# Power_6V.net
KiCad netlist of a schematic drawn in Altium Designer
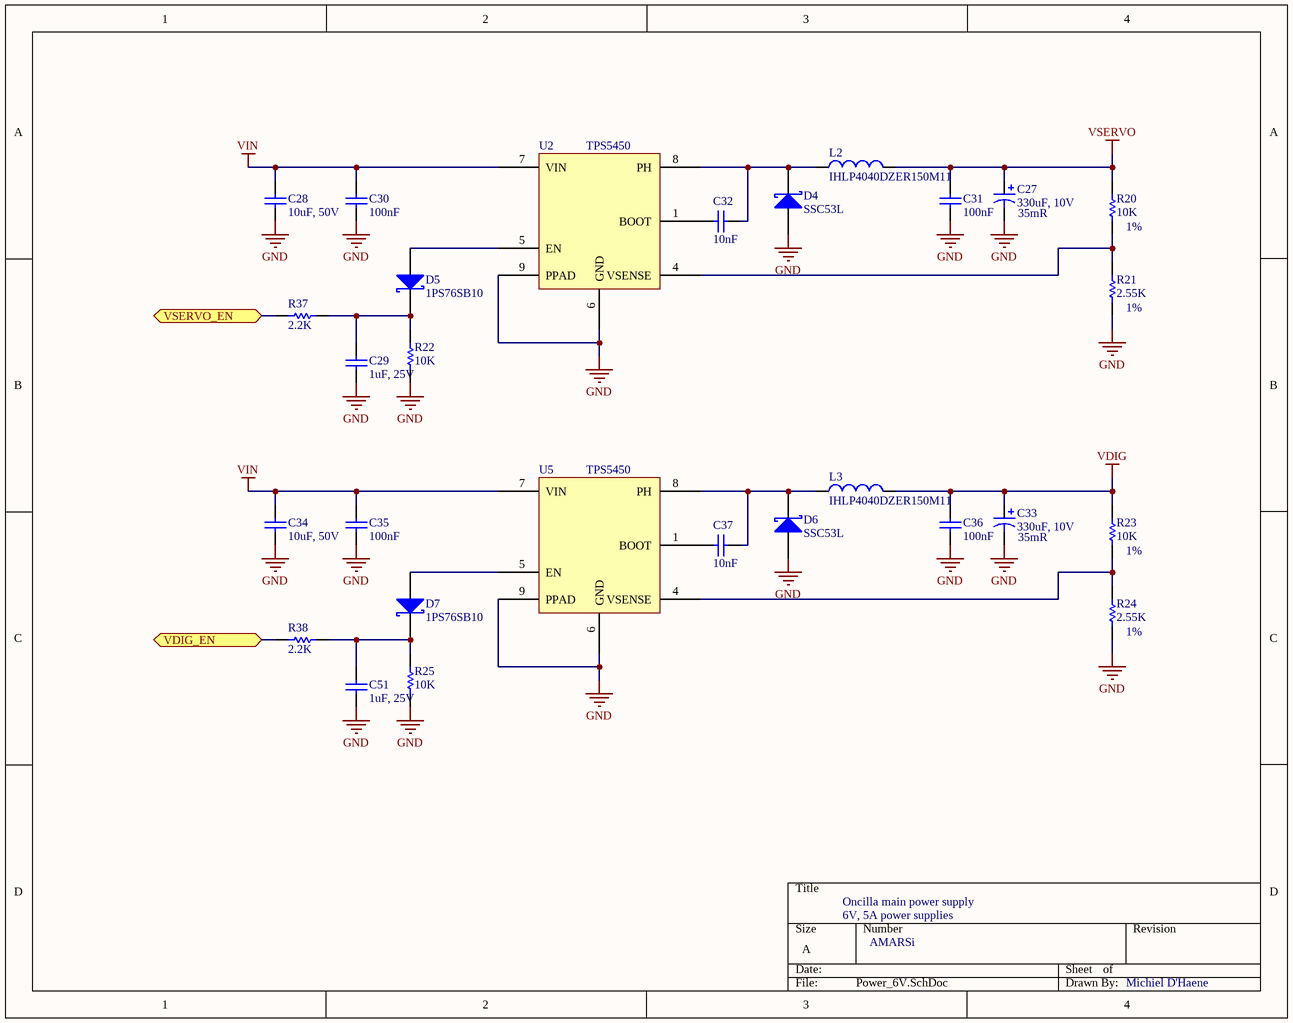
[diagram p0: Power_6V.SchDoc]

(export (version "E")
  (design (tool "Eeschema 10.0.6"))
  (components
    (comp (ref "C27")
      (value "330uF, 10V")
      (footprint "7343")
      (fields (field (name "ESR") "35mR") (field (name "PUBLISHER") "Altium Limited"))
      (libsource (lib "Vishay Sprague Tantalum Chip Capacitor") (part "255D157X06R3D2T045"))
    )
    (comp (ref "C28")
      (value "10uF, 50V")
      (footprint "CAPC3216L")
      (description "Capacitor (Semiconductor SIM Model)")
      (fields (field (name "PUBLISHER") "Altium Limited"))
      (libsource (lib "Miscellaneous Devices") (part "Cap Semi"))
    )
    (comp (ref "C29")
      (value "1uF, 25V")
      (footprint "CAPC1608L")
      (description "Capacitor (Semiconductor SIM Model)")
      (fields (field (name "PUBLISHER") "Altium Limited"))
      (libsource (lib "Miscellaneous Devices") (part "Cap Semi"))
    )
    (comp (ref "C30")
      (value "100nF")
      (footprint "CAPC1608L")
      (description "Capacitor (Semiconductor SIM Model)")
      (fields (field (name "PUBLISHER") "Altium Limited"))
      (libsource (lib "Miscellaneous Devices") (part "Cap Semi"))
    )
    (comp (ref "C31")
      (value "100nF")
      (footprint "CAPC1608L")
      (description "Capacitor (Semiconductor SIM Model)")
      (fields (field (name "PUBLISHER") "Altium Limited"))
      (libsource (lib "Miscellaneous Devices") (part "Cap Semi"))
    )
    (comp (ref "C32")
      (value "10nF")
      (footprint "CAPC1608L")
      (description "Capacitor (Semiconductor SIM Model)")
      (fields (field (name "PUBLISHER") "Altium Limited"))
      (libsource (lib "Miscellaneous Devices") (part "Cap Semi"))
    )
    (comp (ref "C33")
      (value "330uF, 10V")
      (footprint "7343")
      (fields (field (name "ESR") "35mR") (field (name "PUBLISHER") "Altium Limited"))
      (libsource (lib "Vishay Sprague Tantalum Chip Capacitor") (part "255D157X06R3D2T045"))
    )
    (comp (ref "C34")
      (value "10uF, 50V")
      (footprint "CAPC3216L")
      (description "Capacitor (Semiconductor SIM Model)")
      (fields (field (name "PUBLISHER") "Altium Limited"))
      (libsource (lib "Miscellaneous Devices") (part "Cap Semi"))
    )
    (comp (ref "C35")
      (value "100nF")
      (footprint "CAPC1608L")
      (description "Capacitor (Semiconductor SIM Model)")
      (fields (field (name "PUBLISHER") "Altium Limited"))
      (libsource (lib "Miscellaneous Devices") (part "Cap Semi"))
    )
    (comp (ref "C36")
      (value "100nF")
      (footprint "CAPC1608L")
      (description "Capacitor (Semiconductor SIM Model)")
      (fields (field (name "PUBLISHER") "Altium Limited"))
      (libsource (lib "Miscellaneous Devices") (part "Cap Semi"))
    )
    (comp (ref "C37")
      (value "10nF")
      (footprint "CAPC1608L")
      (description "Capacitor (Semiconductor SIM Model)")
      (fields (field (name "PUBLISHER") "Altium Limited"))
      (libsource (lib "Miscellaneous Devices") (part "Cap Semi"))
    )
    (comp (ref "C51")
      (value "1uF, 25V")
      (footprint "CAPC1608L")
      (description "Capacitor (Semiconductor SIM Model)")
      (fields (field (name "PUBLISHER") "Altium Limited"))
      (libsource (lib "Miscellaneous Devices") (part "Cap Semi"))
    )
    (comp (ref "D4")
      (value "SSC53L")
      (footprint "SMC")
      (description "Schottky Rectifier")
      (fields (field (name "PUBLISHER") "Altium Limited"))
      (libsource (lib "IR Rectifier - Schottky") (part "30BQ040"))
    )
    (comp (ref "D5")
      (value "1PS76SB10")
      (footprint "SOD323")
      (description "Schottky Barrier Diode")
      (fields (field (name "PUBLISHER") "Altium Limited"))
      (libsource (lib "Philips Discrete Diode - Schottky") (part "1PS76SB10"))
    )
    (comp (ref "D6")
      (value "SSC53L")
      (footprint "SMC")
      (description "Schottky Rectifier")
      (fields (field (name "PUBLISHER") "Altium Limited"))
      (libsource (lib "IR Rectifier - Schottky") (part "30BQ040"))
    )
    (comp (ref "D7")
      (value "1PS76SB10")
      (footprint "SOD323")
      (description "Schottky Barrier Diode")
      (fields (field (name "PUBLISHER") "Altium Limited"))
      (libsource (lib "Philips Discrete Diode - Schottky") (part "1PS76SB10"))
    )
    (comp (ref "L2")
      (value "IHLP4040DZER150M11")
      (footprint "IHLP-4040DZ")
      (libsource (lib "New_library") (part "Inductor"))
    )
    (comp (ref "L3")
      (value "IHLP4040DZER150M11")
      (footprint "IHLP-4040DZ")
      (libsource (lib "New_library") (part "Inductor"))
    )
    (comp (ref "R20")
      (value "10K")
      (footprint "RESC1608L")
      (description "Semiconductor Resistor")
      (fields
        (field (name "PRECISION") "1%")
        (field (name "Comment") "10k, 1%")
        (field (name "PUBLISHER") "Altium Limited")
      )
      (libsource (lib "Miscellaneous Devices") (part "Res Semi"))
    )
    (comp (ref "R21")
      (value "2.55K")
      (footprint "RESC1608L")
      (description "Semiconductor Resistor")
      (fields
        (field (name "PRECISION") "1%")
        (field (name "Comment") "2.55k, 1%")
        (field (name "PUBLISHER") "Altium Limited")
      )
      (libsource (lib "Miscellaneous Devices") (part "Res Semi"))
    )
    (comp (ref "R22")
      (value "10K")
      (footprint "RESC1608L")
      (description "Semiconductor Resistor")
      (fields (field (name "Comment") "10k") (field (name "PUBLISHER") "Altium Limited"))
      (libsource (lib "Miscellaneous Devices") (part "Res Semi"))
    )
    (comp (ref "R23")
      (value "10K")
      (footprint "RESC1608L")
      (description "Semiconductor Resistor")
      (fields
        (field (name "PRECISION") "1%")
        (field (name "Comment") "10k, 1%")
        (field (name "PUBLISHER") "Altium Limited")
      )
      (libsource (lib "Miscellaneous Devices") (part "Res Semi"))
    )
    (comp (ref "R24")
      (value "2.55K")
      (footprint "RESC1608L")
      (description "Semiconductor Resistor")
      (fields
        (field (name "PRECISION") "1%")
        (field (name "Comment") "2.55k, 1%")
        (field (name "PUBLISHER") "Altium Limited")
      )
      (libsource (lib "Miscellaneous Devices") (part "Res Semi"))
    )
    (comp (ref "R25")
      (value "10K")
      (footprint "RESC1608L")
      (description "Semiconductor Resistor")
      (fields (field (name "Comment") "10k") (field (name "PUBLISHER") "Altium Limited"))
      (libsource (lib "Miscellaneous Devices") (part "Res Semi"))
    )
    (comp (ref "R37")
      (value "2.2K")
      (footprint "RESC1608L")
      (description "Semiconductor Resistor")
      (fields (field (name "Comment") "2.2k") (field (name "PUBLISHER") "Altium Limited"))
      (libsource (lib "Miscellaneous Devices") (part "Res Semi"))
    )
    (comp (ref "R38")
      (value "2.2K")
      (footprint "RESC1608L")
      (description "Semiconductor Resistor")
      (fields (field (name "Comment") "2.2k") (field (name "PUBLISHER") "Altium Limited"))
      (libsource (lib "Miscellaneous Devices") (part "Res Semi"))
    )
    (comp (ref "U2")
      (value "TPS5450")
      (footprint "SOIC8 POWERPAD")
      (libsource (lib "New_library") (part "TPS5450"))
    )
    (comp (ref "U5")
      (value "TPS5450")
      (footprint "SOIC8 POWERPAD")
      (libsource (lib "New_library") (part "TPS5450"))
    )
  )
  (nets
    (net (code "1") (name "/VDIG_EN") (class "Default")
      (node (ref "R38") (pin "2") (pinfunction "2_2") (pintype "passive"))
    )
    (net (code "2") (name "/VSERVO_EN") (class "Default")
      (node (ref "R37") (pin "2") (pinfunction "2_2") (pintype "passive"))
    )
    (net (code "3") (name "GND") (class "Default")
      (node (ref "C27") (pin "2") (pinfunction "2_2") (pintype "passive"))
      (node (ref "C28") (pin "1") (pinfunction "1_1") (pintype "passive"))
      (node (ref "C29") (pin "1") (pinfunction "1_1") (pintype "passive"))
      (node (ref "C30") (pin "1") (pinfunction "1_1") (pintype "passive"))
      (node (ref "C31") (pin "1") (pinfunction "1_1") (pintype "passive"))
      (node (ref "C33") (pin "2") (pinfunction "2_2") (pintype "passive"))
      (node (ref "C34") (pin "1") (pinfunction "1_1") (pintype "passive"))
      (node (ref "C35") (pin "1") (pinfunction "1_1") (pintype "passive"))
      (node (ref "C36") (pin "1") (pinfunction "1_1") (pintype "passive"))
      (node (ref "C51") (pin "1") (pinfunction "1_1") (pintype "passive"))
      (node (ref "D4") (pin "1") (pinfunction "A_1") (pintype "passive"))
      (node (ref "D6") (pin "1") (pinfunction "A_1") (pintype "passive"))
      (node (ref "R21") (pin "1") (pinfunction "1_1") (pintype "passive"))
      (node (ref "R22") (pin "1") (pinfunction "1_1") (pintype "passive"))
      (node (ref "R24") (pin "1") (pinfunction "1_1") (pintype "passive"))
      (node (ref "R25") (pin "1") (pinfunction "1_1") (pintype "passive"))
      (node (ref "U2") (pin "6") (pinfunction "GND_6") (pintype "passive"))
      (node (ref "U2") (pin "9") (pinfunction "PPAD_9") (pintype "passive"))
      (node (ref "U5") (pin "6") (pinfunction "GND_6") (pintype "passive"))
      (node (ref "U5") (pin "9") (pinfunction "PPAD_9") (pintype "passive"))
    )
    (net (code "4") (name "Net-(D4-K)") (class "Default")
      (node (ref "C32") (pin "2") (pinfunction "2_2") (pintype "passive"))
      (node (ref "D4") (pin "2") (pinfunction "K_2") (pintype "passive"))
      (node (ref "L2") (pin "1") (pinfunction "1_1") (pintype "passive"))
      (node (ref "U2") (pin "8") (pinfunction "PH_8") (pintype "passive"))
    )
    (net (code "5") (name "Net-(D5-A)") (class "Default")
      (node (ref "D5") (pin "2") (pinfunction "A_2") (pintype "passive"))
      (node (ref "U2") (pin "5") (pinfunction "EN_5") (pintype "passive"))
    )
    (net (code "6") (name "Net-(D5-K)") (class "Default")
      (node (ref "C29") (pin "2") (pinfunction "2_2") (pintype "passive"))
      (node (ref "D5") (pin "1") (pinfunction "K_1") (pintype "passive"))
      (node (ref "R22") (pin "2") (pinfunction "2_2") (pintype "passive"))
      (node (ref "R37") (pin "1") (pinfunction "1_1") (pintype "passive"))
    )
    (net (code "7") (name "Net-(D6-K)") (class "Default")
      (node (ref "C37") (pin "2") (pinfunction "2_2") (pintype "passive"))
      (node (ref "D6") (pin "2") (pinfunction "K_2") (pintype "passive"))
      (node (ref "L3") (pin "1") (pinfunction "1_1") (pintype "passive"))
      (node (ref "U5") (pin "8") (pinfunction "PH_8") (pintype "passive"))
    )
    (net (code "8") (name "Net-(D7-A)") (class "Default")
      (node (ref "D7") (pin "2") (pinfunction "A_2") (pintype "passive"))
      (node (ref "U5") (pin "5") (pinfunction "EN_5") (pintype "passive"))
    )
    (net (code "9") (name "Net-(D7-K)") (class "Default")
      (node (ref "C51") (pin "2") (pinfunction "2_2") (pintype "passive"))
      (node (ref "D7") (pin "1") (pinfunction "K_1") (pintype "passive"))
      (node (ref "R25") (pin "2") (pinfunction "2_2") (pintype "passive"))
      (node (ref "R38") (pin "1") (pinfunction "1_1") (pintype "passive"))
    )
    (net (code "10") (name "Net-(U2-BOOT)") (class "Default")
      (node (ref "C32") (pin "1") (pinfunction "1_1") (pintype "passive"))
      (node (ref "U2") (pin "1") (pinfunction "BOOT_1") (pintype "passive"))
    )
    (net (code "11") (name "Net-(U2-VSENSE)") (class "Default")
      (node (ref "R20") (pin "1") (pinfunction "1_1") (pintype "passive"))
      (node (ref "R21") (pin "2") (pinfunction "2_2") (pintype "passive"))
      (node (ref "U2") (pin "4") (pinfunction "VSENSE_4") (pintype "passive"))
    )
    (net (code "12") (name "Net-(U5-BOOT)") (class "Default")
      (node (ref "C37") (pin "1") (pinfunction "1_1") (pintype "passive"))
      (node (ref "U5") (pin "1") (pinfunction "BOOT_1") (pintype "passive"))
    )
    (net (code "13") (name "Net-(U5-VSENSE)") (class "Default")
      (node (ref "R23") (pin "1") (pinfunction "1_1") (pintype "passive"))
      (node (ref "R24") (pin "2") (pinfunction "2_2") (pintype "passive"))
      (node (ref "U5") (pin "4") (pinfunction "VSENSE_4") (pintype "passive"))
    )
    (net (code "14") (name "VDIG") (class "Default")
      (node (ref "C33") (pin "1") (pinfunction "1_1") (pintype "passive"))
      (node (ref "C36") (pin "2") (pinfunction "2_2") (pintype "passive"))
      (node (ref "L3") (pin "2") (pinfunction "2_2") (pintype "passive"))
      (node (ref "R23") (pin "2") (pinfunction "2_2") (pintype "passive"))
    )
    (net (code "15") (name "VIN") (class "Default")
      (node (ref "C28") (pin "2") (pinfunction "2_2") (pintype "passive"))
      (node (ref "C30") (pin "2") (pinfunction "2_2") (pintype "passive"))
      (node (ref "C34") (pin "2") (pinfunction "2_2") (pintype "passive"))
      (node (ref "C35") (pin "2") (pinfunction "2_2") (pintype "passive"))
      (node (ref "U2") (pin "7") (pinfunction "VIN_7") (pintype "passive"))
      (node (ref "U5") (pin "7") (pinfunction "VIN_7") (pintype "passive"))
    )
    (net (code "16") (name "VSERVO") (class "Default")
      (node (ref "C27") (pin "1") (pinfunction "1_1") (pintype "passive"))
      (node (ref "C31") (pin "2") (pinfunction "2_2") (pintype "passive"))
      (node (ref "L2") (pin "2") (pinfunction "2_2") (pintype "passive"))
      (node (ref "R20") (pin "2") (pinfunction "2_2") (pintype "passive"))
    )
  )
)
